# 01-POWER.net
KiCad netlist of a schematic drawn in Altium Designer
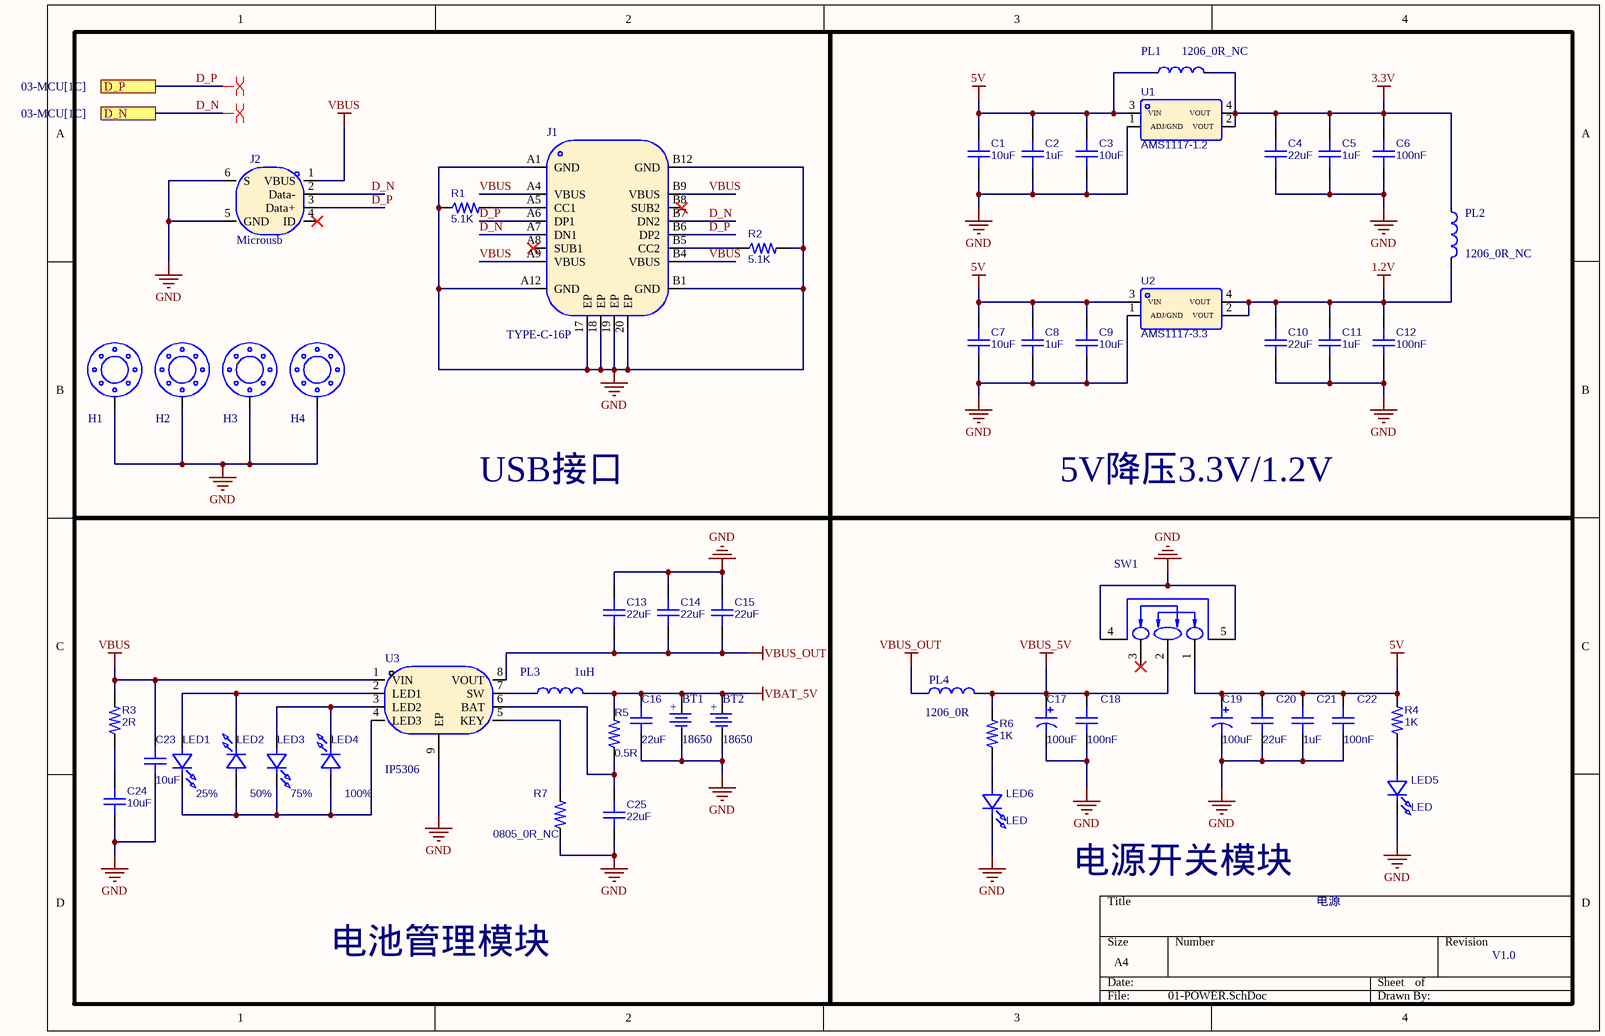
[diagram p0: 01-POWER.SchDoc]

(export (version "E")
  (design (tool "Eeschema 10.0.6"))
  (components
    (comp (ref "BT1")
      (value "18650")
      (footprint "BAT-SMD-18650")
      (description "纽扣电池CR2032-BS-6-1")
      (fields (field (name "MANUFACTURER") "Q&J") (field (name "MANUFACTURER PART") "CR2032-BS-6-1"))
      (libsource (lib "声源跟踪小车原理图库") (part "CR2032"))
    )
    (comp (ref "BT2")
      (value "18650")
      (footprint "BAT-SMD-18650")
      (description "纽扣电池CR2032-BS-6-1")
      (fields (field (name "MANUFACTURER") "Q&J") (field (name "MANUFACTURER PART") "CR2032-BS-6-1"))
      (libsource (lib "声源跟踪小车原理图库") (part "CR2032"))
    )
    (comp (ref "C1")
      (value "10uF")
      (footprint "CAP-SMD-0603")
      (description "贴片电容")
      (fields
        (field (name "BOM_MANUFACTURER PART") "CL03A104KQ3NNNC")
        (field (name "BOM_SUPPLIER PART") "C160831")
        (field (name "CONTRIBUTOR") "LCSC")
      )
      (libsource (lib "声源跟踪小车原理图库") (part "CAP"))
    )
    (comp (ref "C2")
      (value "1uF")
      (footprint "CAP-SMD-0603")
      (description "贴片电容")
      (fields
        (field (name "BOM_MANUFACTURER PART") "CL03A104KQ3NNNC")
        (field (name "BOM_SUPPLIER PART") "C160831")
        (field (name "CONTRIBUTOR") "LCSC")
      )
      (libsource (lib "声源跟踪小车原理图库") (part "CAP"))
    )
    (comp (ref "C3")
      (value "10uF")
      (footprint "CAP-SMD-0603")
      (description "贴片电容")
      (fields
        (field (name "BOM_MANUFACTURER PART") "CL03A104KQ3NNNC")
        (field (name "BOM_SUPPLIER PART") "C160831")
        (field (name "CONTRIBUTOR") "LCSC")
      )
      (libsource (lib "声源跟踪小车原理图库") (part "CAP"))
    )
    (comp (ref "C4")
      (value "22uF")
      (footprint "CAP-SMD-0603")
      (description "贴片电容")
      (fields
        (field (name "BOM_MANUFACTURER PART") "CL03A104KQ3NNNC")
        (field (name "BOM_SUPPLIER PART") "C160831")
        (field (name "CONTRIBUTOR") "LCSC")
      )
      (libsource (lib "声源跟踪小车原理图库") (part "CAP"))
    )
    (comp (ref "C5")
      (value "1uF")
      (footprint "CAP-SMD-0603")
      (description "贴片电容")
      (fields
        (field (name "BOM_MANUFACTURER PART") "CL03A104KQ3NNNC")
        (field (name "BOM_SUPPLIER PART") "C160831")
        (field (name "CONTRIBUTOR") "LCSC")
      )
      (libsource (lib "声源跟踪小车原理图库") (part "CAP"))
    )
    (comp (ref "C6")
      (value "100nF")
      (footprint "CAP-SMD-0603")
      (description "贴片电容")
      (fields
        (field (name "BOM_MANUFACTURER PART") "CL03A104KQ3NNNC")
        (field (name "BOM_SUPPLIER PART") "C160831")
        (field (name "CONTRIBUTOR") "LCSC")
      )
      (libsource (lib "声源跟踪小车原理图库") (part "CAP"))
    )
    (comp (ref "C7")
      (value "10uF")
      (footprint "CAP-SMD-0603")
      (description "贴片电容")
      (fields
        (field (name "BOM_MANUFACTURER PART") "CL03A104KQ3NNNC")
        (field (name "BOM_SUPPLIER PART") "C160831")
        (field (name "CONTRIBUTOR") "LCSC")
      )
      (libsource (lib "声源跟踪小车原理图库") (part "CAP"))
    )
    (comp (ref "C8")
      (value "1uF")
      (footprint "CAP-SMD-0603")
      (description "贴片电容")
      (fields
        (field (name "BOM_MANUFACTURER PART") "CL03A104KQ3NNNC")
        (field (name "BOM_SUPPLIER PART") "C160831")
        (field (name "CONTRIBUTOR") "LCSC")
      )
      (libsource (lib "声源跟踪小车原理图库") (part "CAP"))
    )
    (comp (ref "C9")
      (value "10uF")
      (footprint "CAP-SMD-0603")
      (description "贴片电容")
      (fields
        (field (name "BOM_MANUFACTURER PART") "CL03A104KQ3NNNC")
        (field (name "BOM_SUPPLIER PART") "C160831")
        (field (name "CONTRIBUTOR") "LCSC")
      )
      (libsource (lib "声源跟踪小车原理图库") (part "CAP"))
    )
    (comp (ref "C10")
      (value "22uF")
      (footprint "CAP-SMD-0603")
      (description "贴片电容")
      (fields
        (field (name "BOM_MANUFACTURER PART") "CL03A104KQ3NNNC")
        (field (name "BOM_SUPPLIER PART") "C160831")
        (field (name "CONTRIBUTOR") "LCSC")
      )
      (libsource (lib "声源跟踪小车原理图库") (part "CAP"))
    )
    (comp (ref "C11")
      (value "1uF")
      (footprint "CAP-SMD-0603")
      (description "贴片电容")
      (fields
        (field (name "BOM_MANUFACTURER PART") "CL03A104KQ3NNNC")
        (field (name "BOM_SUPPLIER PART") "C160831")
        (field (name "CONTRIBUTOR") "LCSC")
      )
      (libsource (lib "声源跟踪小车原理图库") (part "CAP"))
    )
    (comp (ref "C12")
      (value "100nF")
      (footprint "CAP-SMD-0603")
      (description "贴片电容")
      (fields
        (field (name "BOM_MANUFACTURER PART") "CL03A104KQ3NNNC")
        (field (name "BOM_SUPPLIER PART") "C160831")
        (field (name "CONTRIBUTOR") "LCSC")
      )
      (libsource (lib "声源跟踪小车原理图库") (part "CAP"))
    )
    (comp (ref "C13")
      (value "22uF")
      (footprint "CAP-SMD-0603")
      (description "贴片电容")
      (fields
        (field (name "BOM_MANUFACTURER PART") "CL03A104KQ3NNNC")
        (field (name "BOM_SUPPLIER PART") "C160831")
        (field (name "CONTRIBUTOR") "LCSC")
      )
      (libsource (lib "声源跟踪小车原理图库") (part "CAP"))
    )
    (comp (ref "C14")
      (value "22uF")
      (footprint "CAP-SMD-0603")
      (description "贴片电容")
      (fields
        (field (name "BOM_MANUFACTURER PART") "CL03A104KQ3NNNC")
        (field (name "BOM_SUPPLIER PART") "C160831")
        (field (name "CONTRIBUTOR") "LCSC")
      )
      (libsource (lib "声源跟踪小车原理图库") (part "CAP"))
    )
    (comp (ref "C15")
      (value "22uF")
      (footprint "CAP-SMD-0603")
      (description "贴片电容")
      (fields
        (field (name "BOM_MANUFACTURER PART") "CL03A104KQ3NNNC")
        (field (name "BOM_SUPPLIER PART") "C160831")
        (field (name "CONTRIBUTOR") "LCSC")
      )
      (libsource (lib "声源跟踪小车原理图库") (part "CAP"))
    )
    (comp (ref "C16")
      (value "22uF")
      (footprint "CAP-SMD-0603")
      (description "贴片电容")
      (fields
        (field (name "BOM_MANUFACTURER PART") "CL03A104KQ3NNNC")
        (field (name "BOM_SUPPLIER PART") "C160831")
        (field (name "CONTRIBUTOR") "LCSC")
      )
      (libsource (lib "声源跟踪小车原理图库") (part "CAP"))
    )
    (comp (ref "C17")
      (value "100uF")
      (footprint "CAPA-TH-5020-P2.0")
      (description "电解电容")
      (fields
        (field (name "BOM_MANUFACTURER PART") "普通黑色470UF 50V")
        (field (name "BOM_SUPPLIER PART") "C34642")
      )
      (libsource (lib "声源跟踪小车原理图库") (part "CAPA"))
    )
    (comp (ref "C18")
      (value "100nF")
      (footprint "CAP-SMD-0603")
      (description "贴片电容")
      (fields
        (field (name "BOM_MANUFACTURER PART") "CL03A104KQ3NNNC")
        (field (name "BOM_SUPPLIER PART") "C160831")
        (field (name "CONTRIBUTOR") "LCSC")
      )
      (libsource (lib "声源跟踪小车原理图库") (part "CAP"))
    )
    (comp (ref "C19")
      (value "100uF")
      (footprint "CAPA-TH-5020-P2.0")
      (description "电解电容")
      (fields
        (field (name "BOM_MANUFACTURER PART") "普通黑色470UF 50V")
        (field (name "BOM_SUPPLIER PART") "C34642")
      )
      (libsource (lib "声源跟踪小车原理图库") (part "CAPA"))
    )
    (comp (ref "C20")
      (value "22uF")
      (footprint "CAP-SMD-0603")
      (description "贴片电容")
      (fields
        (field (name "BOM_MANUFACTURER PART") "CL03A104KQ3NNNC")
        (field (name "BOM_SUPPLIER PART") "C160831")
        (field (name "CONTRIBUTOR") "LCSC")
      )
      (libsource (lib "声源跟踪小车原理图库") (part "CAP"))
    )
    (comp (ref "C21")
      (value "1uF")
      (footprint "CAP-SMD-0603")
      (description "贴片电容")
      (fields
        (field (name "BOM_MANUFACTURER PART") "CL03A104KQ3NNNC")
        (field (name "BOM_SUPPLIER PART") "C160831")
        (field (name "CONTRIBUTOR") "LCSC")
      )
      (libsource (lib "声源跟踪小车原理图库") (part "CAP"))
    )
    (comp (ref "C22")
      (value "100nF")
      (footprint "CAP-SMD-0603")
      (description "贴片电容")
      (fields
        (field (name "BOM_MANUFACTURER PART") "CL03A104KQ3NNNC")
        (field (name "BOM_SUPPLIER PART") "C160831")
        (field (name "CONTRIBUTOR") "LCSC")
      )
      (libsource (lib "声源跟踪小车原理图库") (part "CAP"))
    )
    (comp (ref "C23")
      (value "10uF")
      (footprint "CAP-SMD-0603")
      (description "贴片电容")
      (fields
        (field (name "BOM_MANUFACTURER PART") "CL03A104KQ3NNNC")
        (field (name "BOM_SUPPLIER PART") "C160831")
        (field (name "CONTRIBUTOR") "LCSC")
      )
      (libsource (lib "声源跟踪小车原理图库") (part "CAP"))
    )
    (comp (ref "C24")
      (value "10uF")
      (footprint "CAP-SMD-0603")
      (description "贴片电容")
      (fields
        (field (name "BOM_MANUFACTURER PART") "CL03A104KQ3NNNC")
        (field (name "BOM_SUPPLIER PART") "C160831")
        (field (name "CONTRIBUTOR") "LCSC")
      )
      (libsource (lib "声源跟踪小车原理图库") (part "CAP"))
    )
    (comp (ref "C25")
      (value "22uF")
      (footprint "CAP-SMD-0603")
      (description "贴片电容")
      (fields
        (field (name "BOM_MANUFACTURER PART") "CL03A104KQ3NNNC")
        (field (name "BOM_SUPPLIER PART") "C160831")
        (field (name "CONTRIBUTOR") "LCSC")
      )
      (libsource (lib "声源跟踪小车原理图库") (part "CAP"))
    )
    (comp (ref "H1")
      (value "M3")
      (footprint "M3-5030-0.3")
      (description "M3螺丝孔")
      (libsource (lib "声源跟踪小车原理图库") (part "M3"))
    )
    (comp (ref "H2")
      (value "M3")
      (footprint "M3-5030-0.3")
      (description "M3螺丝孔")
      (libsource (lib "声源跟踪小车原理图库") (part "M3"))
    )
    (comp (ref "H3")
      (value "M3")
      (footprint "M3-5030-0.3")
      (description "M3螺丝孔")
      (libsource (lib "声源跟踪小车原理图库") (part "M3"))
    )
    (comp (ref "H4")
      (value "M3")
      (footprint "M3-5030-0.3")
      (description "M3螺丝孔")
      (libsource (lib "声源跟踪小车原理图库") (part "M3"))
    )
    (comp (ref "J1")
      (value "TYPE-C-16P")
      (footprint "TYPE-C-SMD-16P")
      (description "TYPE-C-16pin")
      (fields
        (field (name "MANUFACTURER") "kinghelm(金航标)")
        (field (name "MANUFACTURER PART") "KH-TYPE-C-16P")
      )
      (libsource (lib "声源跟踪小车原理图库") (part "TYPE-C-16P"))
    )
    (comp (ref "J2")
      (value "Microusb")
      (footprint "Microusb-SMD-5P")
      (description "安卓阶梯型USB接口")
      (fields (field (name "MANUFACTURER") "Amphenol") (field (name "MANUFACTURER PART") "10118194-0001LF"))
      (libsource (lib "声源跟踪小车原理图库") (part "Microusb-5P"))
    )
    (comp (ref "LED1")
      (value "25%")
      (footprint "LED-SMD-0805")
      (description "LED灯,发光二极管")
      (fields
        (field (name "BOM_SUPPLIER PART") "C434447")
        (field (name "BOM_MANUFACTURER PART") "SZYY0402B")
        (field (name "CONTRIBUTOR") "LCSC")
      )
      (libsource (lib "声源跟踪小车原理图库") (part "LED"))
    )
    (comp (ref "LED2")
      (value "50%")
      (footprint "LED-SMD-0805")
      (description "LED灯,发光二极管")
      (fields
        (field (name "BOM_SUPPLIER PART") "C434447")
        (field (name "BOM_MANUFACTURER PART") "SZYY0402B")
        (field (name "CONTRIBUTOR") "LCSC")
      )
      (libsource (lib "声源跟踪小车原理图库") (part "LED"))
    )
    (comp (ref "LED3")
      (value "75%")
      (footprint "LED-SMD-0805")
      (description "LED灯,发光二极管")
      (fields
        (field (name "BOM_SUPPLIER PART") "C434447")
        (field (name "BOM_MANUFACTURER PART") "SZYY0402B")
        (field (name "CONTRIBUTOR") "LCSC")
      )
      (libsource (lib "声源跟踪小车原理图库") (part "LED"))
    )
    (comp (ref "LED4")
      (value "100%")
      (footprint "LED-SMD-0805")
      (description "LED灯,发光二极管")
      (fields
        (field (name "BOM_SUPPLIER PART") "C434447")
        (field (name "BOM_MANUFACTURER PART") "SZYY0402B")
        (field (name "CONTRIBUTOR") "LCSC")
      )
      (libsource (lib "声源跟踪小车原理图库") (part "LED"))
    )
    (comp (ref "LED5")
      (value "LED")
      (footprint "LED-SMD-0805")
      (description "LED灯,发光二极管")
      (fields
        (field (name "BOM_SUPPLIER PART") "C434447")
        (field (name "BOM_MANUFACTURER PART") "SZYY0402B")
        (field (name "CONTRIBUTOR") "LCSC")
      )
      (libsource (lib "声源跟踪小车原理图库") (part "LED"))
    )
    (comp (ref "LED6")
      (value "LED")
      (footprint "LED-SMD-0805")
      (description "LED灯,发光二极管")
      (fields
        (field (name "BOM_SUPPLIER PART") "C434447")
        (field (name "BOM_MANUFACTURER PART") "SZYY0402B")
        (field (name "CONTRIBUTOR") "LCSC")
      )
      (libsource (lib "声源跟踪小车原理图库") (part "LED"))
    )
    (comp (ref "PL1")
      (value "1206_0R_NC")
      (footprint "PL-SMD_4.4X4.2-P3.7")
      (description "电感")
      (fields (field (name "MANUFACTURER") "Sunlord(顺络)") (field (name "MANUFACTURER PART") "GZ1608D121TF"))
      (libsource (lib "声源跟踪小车原理图库") (part "PL-IND"))
    )
    (comp (ref "PL2")
      (value "1206_0R_NC")
      (footprint "PL-SMD_4.4X4.2-P3.7")
      (description "电感")
      (fields (field (name "MANUFACTURER") "Sunlord(顺络)") (field (name "MANUFACTURER PART") "GZ1608D121TF"))
      (libsource (lib "声源跟踪小车原理图库") (part "PL-IND"))
    )
    (comp (ref "PL3")
      (value "1uH")
      (footprint "PL-SMD_4.4X4.2-P3.7")
      (description "电感")
      (fields (field (name "MANUFACTURER") "Sunlord(顺络)") (field (name "MANUFACTURER PART") "GZ1608D121TF"))
      (libsource (lib "声源跟踪小车原理图库") (part "PL-IND"))
    )
    (comp (ref "PL4")
      (value "1206_0R")
      (footprint "PL-SMD_4.4X4.2-P3.7")
      (description "电感")
      (fields (field (name "MANUFACTURER") "Sunlord(顺络)") (field (name "MANUFACTURER PART") "GZ1608D121TF"))
      (libsource (lib "声源跟踪小车原理图库") (part "PL-IND"))
    )
    (comp (ref "R1")
      (value "5.1K")
      (footprint "RES-SMD-0603")
      (description "贴片电阻")
      (fields
        (field (name "BOM_SUPPLIER PART") "C118966")
        (field (name "BOM_MANUFACTURER PART") "3362P-1-104")
        (field (name "CONTRIBUTOR") "LCSC")
      )
      (libsource (lib "声源跟踪小车原理图库") (part "RES"))
    )
    (comp (ref "R2")
      (value "5.1K")
      (footprint "RES-SMD-0603")
      (description "贴片电阻")
      (fields
        (field (name "BOM_SUPPLIER PART") "C118966")
        (field (name "BOM_MANUFACTURER PART") "3362P-1-104")
        (field (name "CONTRIBUTOR") "LCSC")
      )
      (libsource (lib "声源跟踪小车原理图库") (part "RES"))
    )
    (comp (ref "R3")
      (value "2R")
      (footprint "RES-SMD-0603")
      (description "贴片电阻")
      (fields
        (field (name "BOM_SUPPLIER PART") "C118966")
        (field (name "BOM_MANUFACTURER PART") "3362P-1-104")
        (field (name "CONTRIBUTOR") "LCSC")
      )
      (libsource (lib "声源跟踪小车原理图库") (part "RES"))
    )
    (comp (ref "R4")
      (value "1K")
      (footprint "RES-SMD-0603")
      (description "贴片电阻")
      (fields
        (field (name "BOM_SUPPLIER PART") "C118966")
        (field (name "BOM_MANUFACTURER PART") "3362P-1-104")
        (field (name "CONTRIBUTOR") "LCSC")
      )
      (libsource (lib "声源跟踪小车原理图库") (part "RES"))
    )
    (comp (ref "R5")
      (value "0.5R")
      (footprint "RES-SMD-0603")
      (description "贴片电阻")
      (fields
        (field (name "BOM_SUPPLIER PART") "C118966")
        (field (name "BOM_MANUFACTURER PART") "3362P-1-104")
        (field (name "CONTRIBUTOR") "LCSC")
      )
      (libsource (lib "声源跟踪小车原理图库") (part "RES"))
    )
    (comp (ref "R6")
      (value "1K")
      (footprint "RES-SMD-0603")
      (description "贴片电阻")
      (fields
        (field (name "BOM_SUPPLIER PART") "C118966")
        (field (name "BOM_MANUFACTURER PART") "3362P-1-104")
        (field (name "CONTRIBUTOR") "LCSC")
      )
      (libsource (lib "声源跟踪小车原理图库") (part "RES"))
    )
    (comp (ref "R7")
      (value "0805_0R_NC")
      (footprint "RES-SMD-0603")
      (description "贴片电阻")
      (fields
        (field (name "BOM_SUPPLIER PART") "C118966")
        (field (name "BOM_MANUFACTURER PART") "3362P-1-104")
        (field (name "CONTRIBUTOR") "LCSC")
      )
      (libsource (lib "声源跟踪小车原理图库") (part "RES"))
    )
    (comp (ref "SW1")
      (value "SS-12D11G5")
      (footprint "SW-TH-D-P4.8")
      (description "额定电流(DC)：3A 额定电压(DC)：125V 额定电流(AC)：3A 额定电压(AC)：125V")
      (fields (field (name "MANUFACTURER") "XKB Connectivity(中国星坤)"))
      (libsource (lib "声源跟踪小车原理图库") (part "SW-D-3P"))
    )
    (comp (ref "U1")
      (value "AMS1117-1.2")
      (footprint "SOT-223-4-LP5.7-P2.3")
      (description "稳压器芯片")
      (fields
        (field (name "BOM_SUPPLIER PART") "C2718490")
        (field (name "BOM_MANUFACTURER PART") "AMS1117-5.0")
        (field (name "CONTRIBUTOR") "LCSC")
      )
      (libsource (lib "声源跟踪小车原理图库") (part "AMS1117-5.0"))
    )
    (comp (ref "U2")
      (value "AMS1117-3.3")
      (footprint "SOT-223-4-LP5.7-P2.3")
      (description "稳压器芯片")
      (fields
        (field (name "BOM_SUPPLIER PART") "C2718490")
        (field (name "BOM_MANUFACTURER PART") "AMS1117-5.0")
        (field (name "CONTRIBUTOR") "LCSC")
      )
      (libsource (lib "声源跟踪小车原理图库") (part "AMS1117-5.0_1"))
    )
    (comp (ref "U3")
      (value "IP5306")
      (footprint "ESOP-8-LP5.3-P1.27")
      (description "充电电池的类型:-;电池单元组数:-;最大充电电流:-;充满的电池组电压:-;最大供应电压:-;")
      (fields (field (name "MANUFACTURER") "INJOINIC(英集芯)"))
      (libsource (lib "声源跟踪小车原理图库") (part "IP5306"))
    )
  )
  (nets
    (net (code "1") (name "/D_N") (class "Default")
      (node (ref "J1") (pin "A7") (pinfunction "DN1_A7") (pintype "passive"))
      (node (ref "J1") (pin "B7") (pinfunction "DN2_B7") (pintype "passive"))
      (node (ref "J2") (pin "2") (pinfunction "Data-_2") (pintype "passive"))
    )
    (net (code "2") (name "/D_P") (class "Default")
      (node (ref "J1") (pin "A6") (pinfunction "DP1_A6") (pintype "passive"))
      (node (ref "J1") (pin "B6") (pinfunction "DP2_B6") (pintype "passive"))
      (node (ref "J2") (pin "3") (pinfunction "Data+_3") (pintype "passive"))
    )
    (net (code "3") (name "1.2V") (class "Default")
      (node (ref "C10") (pin "2") (pinfunction "2_2") (pintype "passive"))
      (node (ref "C11") (pin "2") (pinfunction "2_2") (pintype "passive"))
      (node (ref "C12") (pin "2") (pinfunction "2_2") (pintype "passive"))
      (node (ref "PL2") (pin "2") (pinfunction "2_2") (pintype "passive"))
      (node (ref "U2") (pin "2") (pinfunction "VOUT_2") (pintype "passive"))
      (node (ref "U2") (pin "4") (pinfunction "VOUT_4") (pintype "passive"))
    )
    (net (code "4") (name "3.3V") (class "Default")
      (node (ref "C4") (pin "2") (pinfunction "2_2") (pintype "passive"))
      (node (ref "C5") (pin "2") (pinfunction "2_2") (pintype "passive"))
      (node (ref "C6") (pin "2") (pinfunction "2_2") (pintype "passive"))
      (node (ref "PL1") (pin "2") (pinfunction "2_2") (pintype "passive"))
      (node (ref "PL2") (pin "1") (pinfunction "1_1") (pintype "passive"))
      (node (ref "U1") (pin "2") (pinfunction "VOUT_2") (pintype "passive"))
      (node (ref "U1") (pin "4") (pinfunction "VOUT_4") (pintype "passive"))
    )
    (net (code "5") (name "5V") (class "Default")
      (node (ref "C1") (pin "2") (pinfunction "2_2") (pintype "passive"))
      (node (ref "C19") (pin "1") (pinfunction "1_1") (pintype "passive"))
      (node (ref "C2") (pin "2") (pinfunction "2_2") (pintype "passive"))
      (node (ref "C20") (pin "2") (pinfunction "2_2") (pintype "passive"))
      (node (ref "C21") (pin "2") (pinfunction "2_2") (pintype "passive"))
      (node (ref "C22") (pin "2") (pinfunction "2_2") (pintype "passive"))
      (node (ref "C3") (pin "2") (pinfunction "2_2") (pintype "passive"))
      (node (ref "C7") (pin "2") (pinfunction "2_2") (pintype "passive"))
      (node (ref "C8") (pin "2") (pinfunction "2_2") (pintype "passive"))
      (node (ref "C9") (pin "2") (pinfunction "2_2") (pintype "passive"))
      (node (ref "PL1") (pin "1") (pinfunction "1_1") (pintype "passive"))
      (node (ref "R4") (pin "2") (pinfunction "2_2") (pintype "passive"))
      (node (ref "SW1") (pin "1") (pinfunction "1_1") (pintype "passive"))
      (node (ref "U1") (pin "3") (pinfunction "VIN_3") (pintype "passive"))
      (node (ref "U2") (pin "3") (pinfunction "VIN_3") (pintype "passive"))
    )
    (net (code "6") (name "GND") (class "Default")
      (node (ref "BT1") (pin "2") (pinfunction "+_2") (pintype "passive"))
      (node (ref "BT2") (pin "2") (pinfunction "+_2") (pintype "passive"))
      (node (ref "C1") (pin "1") (pinfunction "1_1") (pintype "passive"))
      (node (ref "C10") (pin "1") (pinfunction "1_1") (pintype "passive"))
      (node (ref "C11") (pin "1") (pinfunction "1_1") (pintype "passive"))
      (node (ref "C12") (pin "1") (pinfunction "1_1") (pintype "passive"))
      (node (ref "C13") (pin "2") (pinfunction "2_2") (pintype "passive"))
      (node (ref "C14") (pin "2") (pinfunction "2_2") (pintype "passive"))
      (node (ref "C15") (pin "2") (pinfunction "2_2") (pintype "passive"))
      (node (ref "C16") (pin "1") (pinfunction "1_1") (pintype "passive"))
      (node (ref "C17") (pin "2") (pinfunction "2_2") (pintype "passive"))
      (node (ref "C18") (pin "1") (pinfunction "1_1") (pintype "passive"))
      (node (ref "C19") (pin "2") (pinfunction "2_2") (pintype "passive"))
      (node (ref "C2") (pin "1") (pinfunction "1_1") (pintype "passive"))
      (node (ref "C20") (pin "1") (pinfunction "1_1") (pintype "passive"))
      (node (ref "C21") (pin "1") (pinfunction "1_1") (pintype "passive"))
      (node (ref "C22") (pin "1") (pinfunction "1_1") (pintype "passive"))
      (node (ref "C23") (pin "1") (pinfunction "1_1") (pintype "passive"))
      (node (ref "C24") (pin "1") (pinfunction "1_1") (pintype "passive"))
      (node (ref "C25") (pin "1") (pinfunction "1_1") (pintype "passive"))
      (node (ref "C3") (pin "1") (pinfunction "1_1") (pintype "passive"))
      (node (ref "C4") (pin "1") (pinfunction "1_1") (pintype "passive"))
      (node (ref "C5") (pin "1") (pinfunction "1_1") (pintype "passive"))
      (node (ref "C6") (pin "1") (pinfunction "1_1") (pintype "passive"))
      (node (ref "C7") (pin "1") (pinfunction "1_1") (pintype "passive"))
      (node (ref "C8") (pin "1") (pinfunction "1_1") (pintype "passive"))
      (node (ref "C9") (pin "1") (pinfunction "1_1") (pintype "passive"))
      (node (ref "H1") (pin "1") (pinfunction "1_1") (pintype "passive"))
      (node (ref "H2") (pin "1") (pinfunction "1_1") (pintype "passive"))
      (node (ref "H3") (pin "1") (pinfunction "1_1") (pintype "passive"))
      (node (ref "H4") (pin "1") (pinfunction "1_1") (pintype "passive"))
      (node (ref "J1") (pin "17") (pinfunction "EP_17") (pintype "passive"))
      (node (ref "J1") (pin "18") (pinfunction "EP_18") (pintype "passive"))
      (node (ref "J1") (pin "19") (pinfunction "EP_19") (pintype "passive"))
      (node (ref "J1") (pin "20") (pinfunction "EP_20") (pintype "passive"))
      (node (ref "J1") (pin "A1") (pinfunction "GND_A1") (pintype "passive"))
      (node (ref "J1") (pin "A12") (pinfunction "GND_A12") (pintype "passive"))
      (node (ref "J1") (pin "B1") (pinfunction "GND_B1") (pintype "passive"))
      (node (ref "J1") (pin "B12") (pinfunction "GND_B12") (pintype "passive"))
      (node (ref "J2") (pin "5") (pinfunction "GND_5") (pintype "passive"))
      (node (ref "J2") (pin "6") (pinfunction "S_6") (pintype "passive"))
      (node (ref "LED5") (pin "2") (pinfunction "K_2") (pintype "passive"))
      (node (ref "LED6") (pin "2") (pinfunction "K_2") (pintype "passive"))
      (node (ref "R1") (pin "1") (pinfunction "1_1") (pintype "passive"))
      (node (ref "R2") (pin "2") (pinfunction "2_2") (pintype "passive"))
      (node (ref "R7") (pin "1") (pinfunction "1_1") (pintype "passive"))
      (node (ref "SW1") (pin "4") (pinfunction "4_4") (pintype "passive"))
      (node (ref "SW1") (pin "5") (pinfunction "5_5") (pintype "passive"))
      (node (ref "U1") (pin "1") (pinfunction "ADJ/GND_1") (pintype "passive"))
      (node (ref "U2") (pin "1") (pinfunction "ADJ/GND_1") (pintype "passive"))
      (node (ref "U3") (pin "9") (pinfunction "EP_9") (pintype "passive"))
    )
    (net (code "7") (name "Net-(C24-Pad2)") (class "Default")
      (node (ref "C24") (pin "2") (pinfunction "2_2") (pintype "passive"))
      (node (ref "R3") (pin "1") (pinfunction "1_1") (pintype "passive"))
    )
    (net (code "8") (name "Net-(J1-CC1)") (class "Default")
      (node (ref "J1") (pin "A5") (pinfunction "CC1_A5") (pintype "passive"))
      (node (ref "R1") (pin "2") (pinfunction "2_2") (pintype "passive"))
    )
    (net (code "9") (name "Net-(J1-CC2)") (class "Default")
      (node (ref "J1") (pin "B5") (pinfunction "CC2_B5") (pintype "passive"))
      (node (ref "R2") (pin "1") (pinfunction "1_1") (pintype "passive"))
    )
    (net (code "10") (name "Net-(LED1-A)") (class "Default")
      (node (ref "LED1") (pin "1") (pinfunction "A_1") (pintype "passive"))
      (node (ref "LED2") (pin "2") (pinfunction "K_2") (pintype "passive"))
      (node (ref "U3") (pin "2") (pinfunction "LED1_2") (pintype "passive"))
    )
    (net (code "11") (name "Net-(LED1-K)") (class "Default")
      (node (ref "LED1") (pin "2") (pinfunction "K_2") (pintype "passive"))
      (node (ref "LED2") (pin "1") (pinfunction "A_1") (pintype "passive"))
      (node (ref "LED3") (pin "2") (pinfunction "K_2") (pintype "passive"))
      (node (ref "LED4") (pin "1") (pinfunction "A_1") (pintype "passive"))
      (node (ref "U3") (pin "4") (pinfunction "LED3_4") (pintype "passive"))
    )
    (net (code "12") (name "Net-(LED3-A)") (class "Default")
      (node (ref "LED3") (pin "1") (pinfunction "A_1") (pintype "passive"))
      (node (ref "LED4") (pin "2") (pinfunction "K_2") (pintype "passive"))
      (node (ref "U3") (pin "3") (pinfunction "LED2_3") (pintype "passive"))
    )
    (net (code "13") (name "Net-(LED5-A)") (class "Default")
      (node (ref "LED5") (pin "1") (pinfunction "A_1") (pintype "passive"))
      (node (ref "R4") (pin "1") (pinfunction "1_1") (pintype "passive"))
    )
    (net (code "14") (name "Net-(LED6-A)") (class "Default")
      (node (ref "LED6") (pin "1") (pinfunction "A_1") (pintype "passive"))
      (node (ref "R6") (pin "1") (pinfunction "1_1") (pintype "passive"))
    )
    (net (code "15") (name "Net-(U3-BAT)") (class "Default")
      (node (ref "C25") (pin "2") (pinfunction "2_2") (pintype "passive"))
      (node (ref "R5") (pin "1") (pinfunction "1_1") (pintype "passive"))
      (node (ref "U3") (pin "6") (pinfunction "BAT_6") (pintype "passive"))
    )
    (net (code "16") (name "Net-(U3-KEY)") (class "Default")
      (node (ref "R7") (pin "2") (pinfunction "2_2") (pintype "passive"))
      (node (ref "U3") (pin "5") (pinfunction "KEY_5") (pintype "passive"))
    )
    (net (code "17") (name "Net-(U3-SW)") (class "Default")
      (node (ref "PL3") (pin "1") (pinfunction "1_1") (pintype "passive"))
      (node (ref "U3") (pin "7") (pinfunction "SW_7") (pintype "passive"))
    )
    (net (code "18") (name "VBAT_5V") (class "Default")
      (node (ref "BT1") (pin "1") (pinfunction "-_1") (pintype "passive"))
      (node (ref "BT2") (pin "1") (pinfunction "-_1") (pintype "passive"))
      (node (ref "C16") (pin "2") (pinfunction "2_2") (pintype "passive"))
      (node (ref "PL3") (pin "2") (pinfunction "2_2") (pintype "passive"))
      (node (ref "R5") (pin "2") (pinfunction "2_2") (pintype "passive"))
    )
    (net (code "19") (name "VBUS") (class "Default")
      (node (ref "C23") (pin "2") (pinfunction "2_2") (pintype "passive"))
      (node (ref "J1") (pin "A4") (pinfunction "VBUS_A4") (pintype "passive"))
      (node (ref "J1") (pin "A9") (pinfunction "VBUS_A9") (pintype "passive"))
      (node (ref "J1") (pin "B4") (pinfunction "VBUS_B4") (pintype "passive"))
      (node (ref "J1") (pin "B9") (pinfunction "VBUS_B9") (pintype "passive"))
      (node (ref "J2") (pin "1") (pinfunction "VBUS_1") (pintype "passive"))
      (node (ref "R3") (pin "2") (pinfunction "2_2") (pintype "passive"))
      (node (ref "U3") (pin "1") (pinfunction "VIN_1") (pintype "passive"))
    )
    (net (code "20") (name "VBUS_5V") (class "Default")
      (node (ref "C17") (pin "1") (pinfunction "1_1") (pintype "passive"))
      (node (ref "C18") (pin "2") (pinfunction "2_2") (pintype "passive"))
      (node (ref "PL4") (pin "2") (pinfunction "2_2") (pintype "passive"))
      (node (ref "R6") (pin "2") (pinfunction "2_2") (pintype "passive"))
      (node (ref "SW1") (pin "2") (pinfunction "2_2") (pintype "passive"))
    )
    (net (code "21") (name "VBUS_OUT") (class "Default")
      (node (ref "C13") (pin "1") (pinfunction "1_1") (pintype "passive"))
      (node (ref "C14") (pin "1") (pinfunction "1_1") (pintype "passive"))
      (node (ref "C15") (pin "1") (pinfunction "1_1") (pintype "passive"))
      (node (ref "PL4") (pin "1") (pinfunction "1_1") (pintype "passive"))
      (node (ref "U3") (pin "8") (pinfunction "VOUT_8") (pintype "passive"))
    )
    (net (code "22") (name "unconnected-(J1-SUB1-PadA8)") (class "Default")
      (node (ref "J1") (pin "A8") (pinfunction "SUB1_A8") (pintype "passive+no_connect"))
    )
    (net (code "23") (name "unconnected-(J1-SUB2-PadB8)") (class "Default")
      (node (ref "J1") (pin "B8") (pinfunction "SUB2_B8") (pintype "passive+no_connect"))
    )
    (net (code "24") (name "unconnected-(J2-ID-Pad4)") (class "Default")
      (node (ref "J2") (pin "4") (pinfunction "ID_4") (pintype "passive+no_connect"))
    )
    (net (code "25") (name "unconnected-(SW1-Pad3)") (class "Default")
      (node (ref "SW1") (pin "3") (pinfunction "3_3") (pintype "passive+no_connect"))
    )
  )
)
